# FTDIProgrammer.net
KiCad netlist of a schematic drawn in Altium Designer
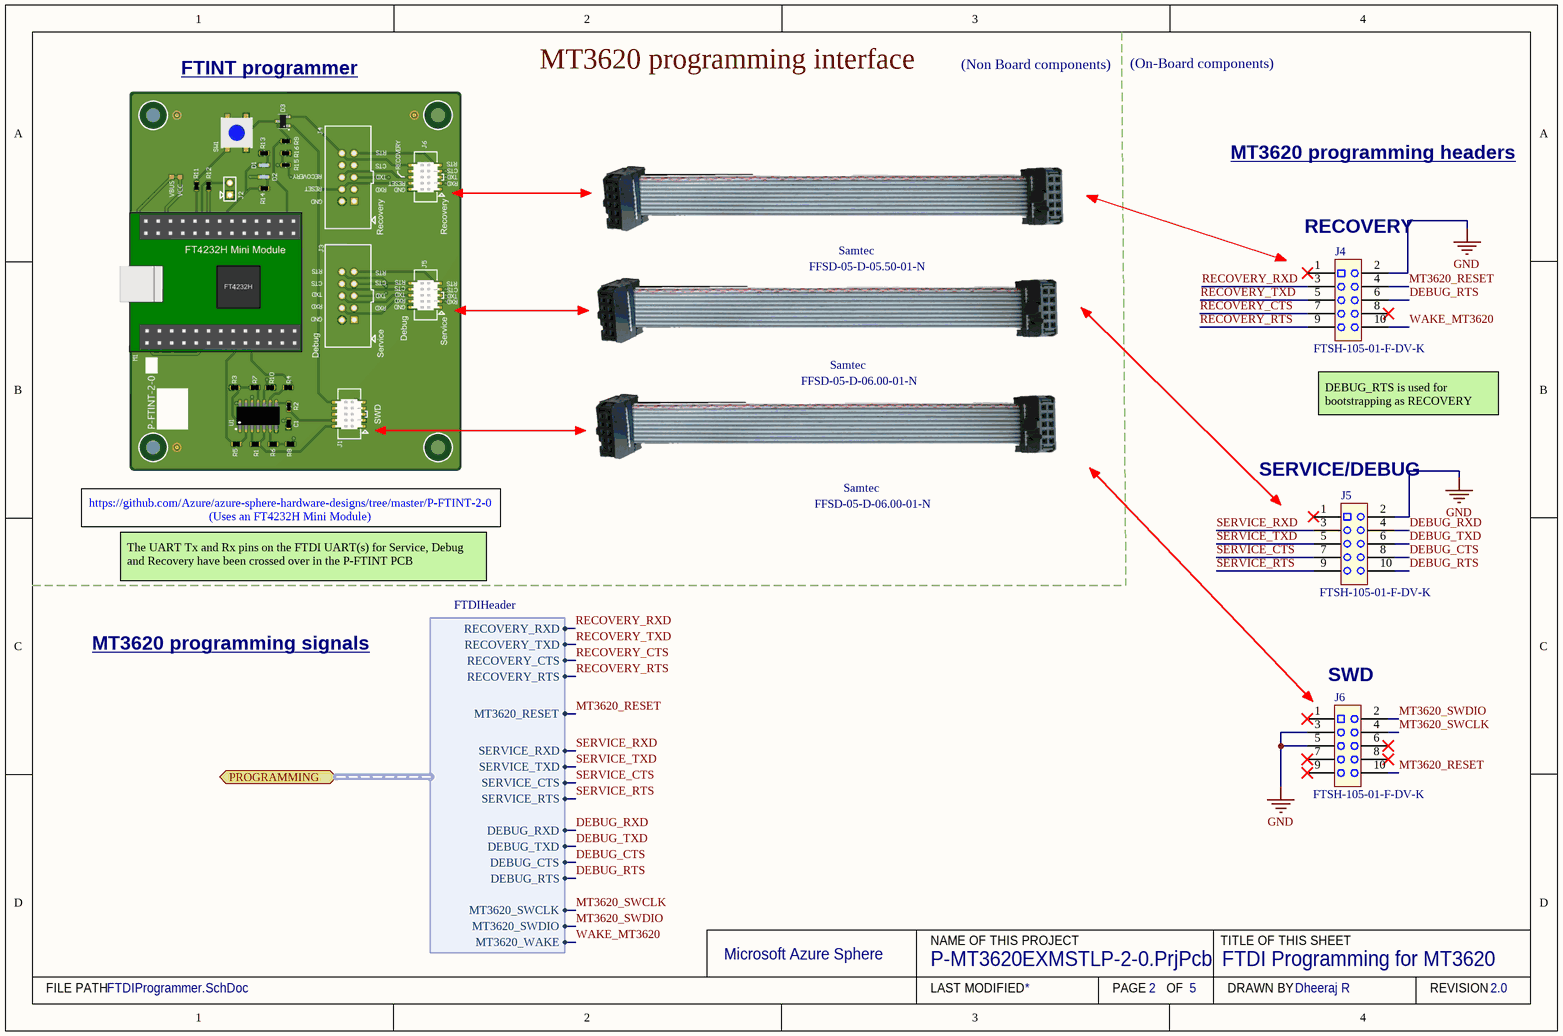
[diagram p0: FTDIProgrammer.SchDoc]

(export (version "E")
  (design (tool "Eeschema 10.0.6"))
  (components
    (comp (ref "J4")
      (value "FTSH-105-01-F-DV-K")
      (footprint "SAMTEC-FTSH-105-01-X-DV-K")
      (description "CONN HEADER 10POS DUAL .05\" SMD")
      (fields (field (name "MANUFACTURER") "Samtec Inc."))
      (libsource (lib "Samtec") (part "FTSH-105-01-F-DV-K"))
    )
    (comp (ref "J5")
      (value "FTSH-105-01-F-DV-K")
      (footprint "SAMTEC-FTSH-105-01-X-DV-K")
      (description "CONN HEADER 10POS DUAL .05\" SMD")
      (fields (field (name "MANUFACTURER") "Samtec Inc."))
      (libsource (lib "Samtec") (part "FTSH-105-01-F-DV-K"))
    )
    (comp (ref "J6")
      (value "FTSH-105-01-F-DV-K")
      (footprint "SAMTEC-FTSH-105-01-X-DV-K")
      (description "CONN HEADER 10POS DUAL .05\" SMD")
      (fields (field (name "MANUFACTURER") "Samtec Inc."))
      (libsource (lib "Samtec") (part "FTSH-105-01-F-DV-K"))
    )
  )
  (nets
    (net (code "2") (name "/DEBUG_CTS") (class "Default")
      (node (ref "J5") (pin "8") (pinfunction "8_8") (pintype "passive"))
    )
    (net (code "3") (name "/DEBUG_RTS") (class "Default")
      (node (ref "J4") (pin "6") (pinfunction "6_6") (pintype "passive"))
      (node (ref "J5") (pin "10") (pinfunction "10_10") (pintype "passive"))
    )
    (net (code "4") (name "/DEBUG_RXD") (class "Default")
      (node (ref "J5") (pin "4") (pinfunction "4_4") (pintype "passive"))
    )
    (net (code "5") (name "/DEBUG_TXD") (class "Default")
      (node (ref "J5") (pin "6") (pinfunction "6_6") (pintype "passive"))
    )
    (net (code "6") (name "/MT3620_RESET") (class "Default")
      (node (ref "J4") (pin "4") (pinfunction "4_4") (pintype "passive"))
      (node (ref "J6") (pin "10") (pinfunction "10_10") (pintype "passive"))
    )
    (net (code "7") (name "/MT3620_SWCLK") (class "Default")
      (node (ref "J6") (pin "4") (pinfunction "4_4") (pintype "passive"))
    )
    (net (code "8") (name "/MT3620_SWDIO") (class "Default")
      (node (ref "J6") (pin "2") (pinfunction "2_2") (pintype "passive"))
    )
    (net (code "9") (name "/RECOVERY_CTS") (class "Default")
      (node (ref "J4") (pin "7") (pinfunction "7_7") (pintype "passive"))
    )
    (net (code "10") (name "/RECOVERY_RTS") (class "Default")
      (node (ref "J4") (pin "9") (pinfunction "9_9") (pintype "passive"))
    )
    (net (code "11") (name "/RECOVERY_RXD") (class "Default")
      (node (ref "J4") (pin "3") (pinfunction "3_3") (pintype "passive"))
    )
    (net (code "12") (name "/RECOVERY_TXD") (class "Default")
      (node (ref "J4") (pin "5") (pinfunction "5_5") (pintype "passive"))
    )
    (net (code "13") (name "/SERVICE_CTS") (class "Default")
      (node (ref "J5") (pin "7") (pinfunction "7_7") (pintype "passive"))
    )
    (net (code "14") (name "/SERVICE_RTS") (class "Default")
      (node (ref "J5") (pin "9") (pinfunction "9_9") (pintype "passive"))
    )
    (net (code "15") (name "/SERVICE_RXD") (class "Default")
      (node (ref "J5") (pin "3") (pinfunction "3_3") (pintype "passive"))
    )
    (net (code "16") (name "/SERVICE_TXD") (class "Default")
      (node (ref "J5") (pin "5") (pinfunction "5_5") (pintype "passive"))
    )
    (net (code "17") (name "/WAKE_MT3620") (class "Default")
      (node (ref "J4") (pin "10") (pinfunction "10_10") (pintype "passive"))
    )
    (net (code "19") (name "GND") (class "Default")
      (node (ref "J4") (pin "2") (pinfunction "2_2") (pintype "passive"))
      (node (ref "J5") (pin "2") (pinfunction "2_2") (pintype "passive"))
      (node (ref "J6") (pin "3") (pinfunction "3_3") (pintype "passive"))
      (node (ref "J6") (pin "5") (pinfunction "5_5") (pintype "passive"))
    )
    (net (code "20") (name "unconnected-(J4-Pad1)") (class "Default")
      (node (ref "J4") (pin "1") (pinfunction "1_1") (pintype "passive+no_connect"))
    )
    (net (code "21") (name "unconnected-(J4-Pad8)") (class "Default")
      (node (ref "J4") (pin "8") (pinfunction "8_8") (pintype "passive+no_connect"))
    )
    (net (code "22") (name "unconnected-(J5-Pad1)") (class "Default")
      (node (ref "J5") (pin "1") (pinfunction "1_1") (pintype "passive+no_connect"))
    )
    (net (code "23") (name "unconnected-(J6-Pad1)") (class "Default")
      (node (ref "J6") (pin "1") (pinfunction "1_1") (pintype "passive+no_connect"))
    )
    (net (code "24") (name "unconnected-(J6-Pad6)") (class "Default")
      (node (ref "J6") (pin "6") (pinfunction "6_6") (pintype "passive+no_connect"))
    )
    (net (code "25") (name "unconnected-(J6-Pad7)") (class "Default")
      (node (ref "J6") (pin "7") (pinfunction "7_7") (pintype "passive+no_connect"))
    )
    (net (code "26") (name "unconnected-(J6-Pad8)") (class "Default")
      (node (ref "J6") (pin "8") (pinfunction "8_8") (pintype "passive+no_connect"))
    )
    (net (code "27") (name "unconnected-(J6-Pad9)") (class "Default")
      (node (ref "J6") (pin "9") (pinfunction "9_9") (pintype "passive+no_connect"))
    )
  )
)
